# HDMI.net
KiCad netlist of a schematic drawn in Altium Designer
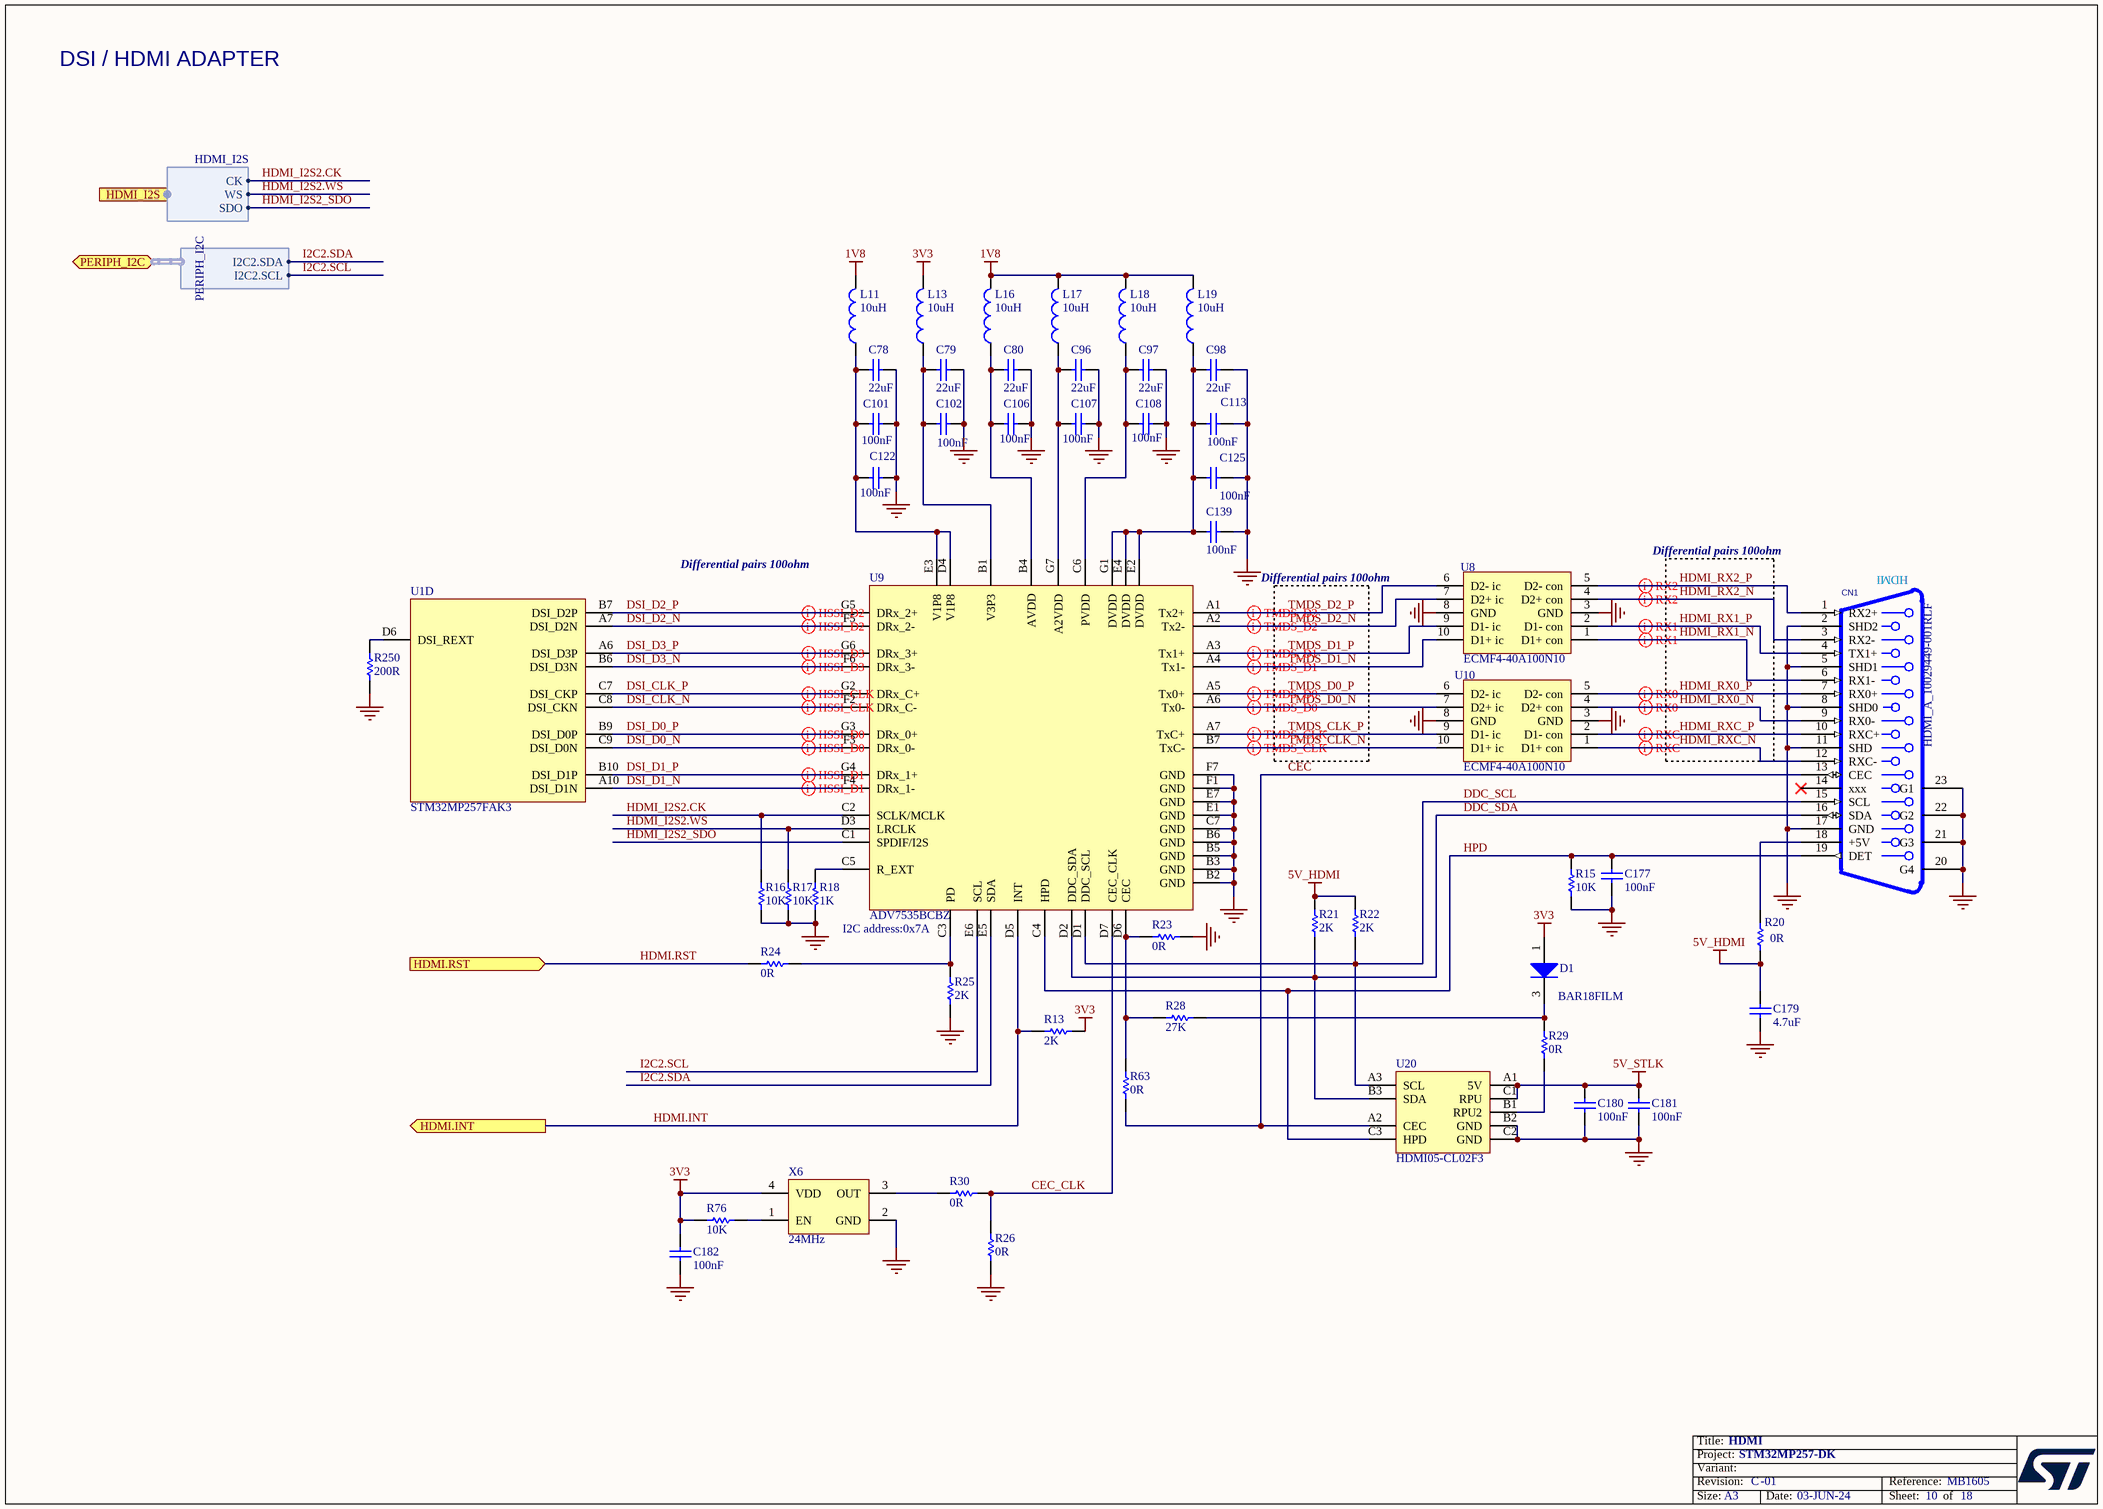
[diagram p0: HDMI.SchDoc]

(export (version "E")
  (design (tool "Eeschema 10.0.6"))
  (components
    (comp (ref "C78")
      (value "22uF")
      (footprint "C0603")
      (description "Capacitor, MLCC, 22uF, 6V3, X5R, +/-20%, 0603, T=0.8mm")
      (fields (field (name "INTERNAL_PART_NUMBER") "MCD-00100") (field (name "MANUFACTURER") "MURATA"))
      (libsource (lib "MCD_PARTS_database") (part "Capacitor"))
    )
    (comp (ref "C79")
      (value "22uF")
      (footprint "C0603")
      (description "Capacitor, MLCC, 22uF, 6V3, X5R, +/-20%, 0603, T=0.8mm")
      (fields (field (name "INTERNAL_PART_NUMBER") "MCD-00100") (field (name "MANUFACTURER") "MURATA"))
      (libsource (lib "MCD_PARTS_database") (part "Capacitor"))
    )
    (comp (ref "C80")
      (value "22uF")
      (footprint "C0603")
      (description "Capacitor, MLCC, 22uF, 6V3, X5R, +/-20%, 0603, T=0.8mm")
      (fields (field (name "INTERNAL_PART_NUMBER") "MCD-00100") (field (name "MANUFACTURER") "MURATA"))
      (libsource (lib "MCD_PARTS_database") (part "Capacitor"))
    )
    (comp (ref "C96")
      (value "22uF")
      (footprint "C0603")
      (description "Capacitor, MLCC, 22uF, 6V3, X5R, +/-20%, 0603, T=0.8mm")
      (fields (field (name "INTERNAL_PART_NUMBER") "MCD-00100") (field (name "MANUFACTURER") "MURATA"))
      (libsource (lib "MCD_PARTS_database") (part "Capacitor"))
    )
    (comp (ref "C97")
      (value "22uF")
      (footprint "C0603")
      (description "Capacitor, MLCC, 22uF, 6V3, X5R, +/-20%, 0603, T=0.8mm")
      (fields (field (name "INTERNAL_PART_NUMBER") "MCD-00100") (field (name "MANUFACTURER") "MURATA"))
      (libsource (lib "MCD_PARTS_database") (part "Capacitor"))
    )
    (comp (ref "C98")
      (value "22uF")
      (footprint "C0603")
      (description "Capacitor, MLCC, 22uF, 6V3, X5R, +/-20%, 0603, T=0.8mm")
      (fields (field (name "INTERNAL_PART_NUMBER") "MCD-00100") (field (name "MANUFACTURER") "MURATA"))
      (libsource (lib "MCD_PARTS_database") (part "Capacitor"))
    )
    (comp (ref "C101")
      (value "100nF")
      (footprint "C0402")
      (description "Capacitor, MLCC, 100nF, 16V, X7R, +/-10%, 0402, T=0.5mm")
      (fields (field (name "INTERNAL_PART_NUMBER") "MCD-00006") (field (name "MANUFACTURER") "YAGEO"))
      (libsource (lib "MCD_PARTS_database") (part "Capacitor"))
    )
    (comp (ref "C102")
      (value "100nF")
      (footprint "C0402")
      (description "Capacitor, MLCC, 100nF, 16V, X7R, +/-10%, 0402, T=0.5mm")
      (fields (field (name "INTERNAL_PART_NUMBER") "MCD-00006") (field (name "MANUFACTURER") "YAGEO"))
      (libsource (lib "MCD_PARTS_database") (part "Capacitor"))
    )
    (comp (ref "C106")
      (value "100nF")
      (footprint "C0402")
      (description "Capacitor, MLCC, 100nF, 16V, X7R, +/-10%, 0402, T=0.5mm")
      (fields (field (name "INTERNAL_PART_NUMBER") "MCD-00006") (field (name "MANUFACTURER") "YAGEO"))
      (libsource (lib "MCD_PARTS_database") (part "Capacitor"))
    )
    (comp (ref "C107")
      (value "100nF")
      (footprint "C0402")
      (description "Capacitor, MLCC, 100nF, 16V, X7R, +/-10%, 0402, T=0.5mm")
      (fields (field (name "INTERNAL_PART_NUMBER") "MCD-00006") (field (name "MANUFACTURER") "YAGEO"))
      (libsource (lib "MCD_PARTS_database") (part "Capacitor"))
    )
    (comp (ref "C108")
      (value "100nF")
      (footprint "C0402")
      (description "Capacitor, MLCC, 100nF, 16V, X7R, +/-10%, 0402, T=0.5mm")
      (fields (field (name "INTERNAL_PART_NUMBER") "MCD-00006") (field (name "MANUFACTURER") "YAGEO"))
      (libsource (lib "MCD_PARTS_database") (part "Capacitor"))
    )
    (comp (ref "C113")
      (value "100nF")
      (footprint "C0402")
      (description "Capacitor, MLCC, 100nF, 16V, X7R, +/-10%, 0402, T=0.5mm")
      (fields (field (name "INTERNAL_PART_NUMBER") "MCD-00006") (field (name "MANUFACTURER") "YAGEO"))
      (libsource (lib "MCD_PARTS_database") (part "Capacitor"))
    )
    (comp (ref "C122")
      (value "100nF")
      (footprint "C0402")
      (description "Capacitor, MLCC, 100nF, 16V, X7R, +/-10%, 0402, T=0.5mm")
      (fields (field (name "INTERNAL_PART_NUMBER") "MCD-00006") (field (name "MANUFACTURER") "YAGEO"))
      (libsource (lib "MCD_PARTS_database") (part "Capacitor"))
    )
    (comp (ref "C125")
      (value "100nF")
      (footprint "C0402")
      (description "Capacitor, MLCC, 100nF, 16V, X7R, +/-10%, 0402, T=0.5mm")
      (fields (field (name "INTERNAL_PART_NUMBER") "MCD-00006") (field (name "MANUFACTURER") "YAGEO"))
      (libsource (lib "MCD_PARTS_database") (part "Capacitor"))
    )
    (comp (ref "C139")
      (value "100nF")
      (footprint "C0402")
      (description "Capacitor, MLCC, 100nF, 16V, X7R, +/-10%, 0402, T=0.5mm")
      (fields (field (name "INTERNAL_PART_NUMBER") "MCD-00006") (field (name "MANUFACTURER") "YAGEO"))
      (libsource (lib "MCD_PARTS_database") (part "Capacitor"))
    )
    (comp (ref "C177")
      (value "100nF")
      (footprint "C0402")
      (description "Capacitor, MLCC, 100nF, 16V, X7R, +/-10%, 0402, T=0.5mm")
      (fields (field (name "INTERNAL_PART_NUMBER") "MCD-00006") (field (name "MANUFACTURER") "YAGEO"))
      (libsource (lib "MCD_PARTS_database") (part "Capacitor"))
    )
    (comp (ref "C179")
      (value "4.7uF")
      (footprint "C0402")
      (description "Capacitor, MLCC, 4.7uF, 6V3, X5R, +/-20%, 0402, T=0.5mm")
      (fields (field (name "INTERNAL_PART_NUMBER") "MCD-01356") (field (name "MANUFACTURER") "MURATA"))
      (libsource (lib "MCD_PARTS_database") (part "Capacitor"))
    )
    (comp (ref "C180")
      (value "100nF")
      (footprint "C0402")
      (description "Capacitor, MLCC, 100nF, 16V, X7R, +/-10%, 0402, T=0.5mm")
      (fields (field (name "INTERNAL_PART_NUMBER") "MCD-00006") (field (name "MANUFACTURER") "YAGEO"))
      (libsource (lib "MCD_PARTS_database") (part "Capacitor"))
    )
    (comp (ref "C181")
      (value "100nF")
      (footprint "C0402")
      (description "Capacitor, MLCC, 100nF, 16V, X7R, +/-10%, 0402, T=0.5mm")
      (fields (field (name "INTERNAL_PART_NUMBER") "MCD-00006") (field (name "MANUFACTURER") "YAGEO"))
      (libsource (lib "MCD_PARTS_database") (part "Capacitor"))
    )
    (comp (ref "C182")
      (value "100nF")
      (footprint "C0402")
      (description "Capacitor, MLCC, 100nF, 16V, X7R, +/-10%, 0402, T=0.5mm")
      (fields (field (name "INTERNAL_PART_NUMBER") "MCD-00006") (field (name "MANUFACTURER") "YAGEO"))
      (libsource (lib "MCD_PARTS_database") (part "Capacitor"))
    )
    (comp (ref "CN1")
      (value "HDMI_A_10029449-001RLF")
      (footprint "CON_HDMI_FCI-AMPHENOL_10029449-001RLF")
      (description "HDMI_Type A, Receptacle, 19x1, 0.5mm, VR, SMD, T= 6.1mm")
      (fields (field (name "INTERNAL_PART_NUMBER") "MCD-00307") (field (name "MANUFACTURER") "AMPHENOL ICC"))
      (libsource (lib "MCD_PARTS_database") (part "HDMI_TypeA_DB19_7"))
    )
    (comp (ref "D1")
      (value "BAR18FILM")
      (footprint "DIO_SOT23_SC59_1A_2NC_3K_H1P4")
      (description "Diode, Ultrafast and RF switching diode, VF=0.41V@IF=1mA, VBR=70V")
      (fields
        (field (name "INTERNAL_PART_NUMBER") "MCD-02333")
        (field (name "MANUFACTURER") "STMICROELECTRONICS")
      )
      (libsource (lib "MCD_PARTS_database") (part "DIODE_SOT23"))
    )
    (comp (ref "L11")
      (value "10uH")
      (footprint "IND_0805_MURATA_LQM21")
      (description "Inductor, 10uH, +/-20%, Isat 100mA, DCR 0.5Ohm,")
      (fields (field (name "INTERNAL_PART_NUMBER") "MCD-02317") (field (name "MANUFACTURER") "MURATA"))
      (libsource (lib "MCD_PARTS_database") (part "Inductor"))
    )
    (comp (ref "L13")
      (value "10uH")
      (footprint "IND_0805_MURATA_LQM21")
      (description "Inductor, 10uH, +/-20%, Isat 100mA, DCR 0.5Ohm,")
      (fields (field (name "INTERNAL_PART_NUMBER") "MCD-02317") (field (name "MANUFACTURER") "MURATA"))
      (libsource (lib "MCD_PARTS_database") (part "Inductor"))
    )
    (comp (ref "L16")
      (value "10uH")
      (footprint "IND_0805_MURATA_LQM21")
      (description "Inductor, 10uH, +/-20%, Isat 100mA, DCR 0.5Ohm,")
      (fields (field (name "INTERNAL_PART_NUMBER") "MCD-02317") (field (name "MANUFACTURER") "MURATA"))
      (libsource (lib "MCD_PARTS_database") (part "Inductor"))
    )
    (comp (ref "L17")
      (value "10uH")
      (footprint "IND_0805_MURATA_LQM21")
      (description "Inductor, 10uH, +/-20%, Isat 100mA, DCR 0.5Ohm,")
      (fields (field (name "INTERNAL_PART_NUMBER") "MCD-02317") (field (name "MANUFACTURER") "MURATA"))
      (libsource (lib "MCD_PARTS_database") (part "Inductor"))
    )
    (comp (ref "L18")
      (value "10uH")
      (footprint "IND_0805_MURATA_LQM21")
      (description "Inductor, 10uH, +/-20%, Isat 100mA, DCR 0.5Ohm,")
      (fields (field (name "INTERNAL_PART_NUMBER") "MCD-02317") (field (name "MANUFACTURER") "MURATA"))
      (libsource (lib "MCD_PARTS_database") (part "Inductor"))
    )
    (comp (ref "L19")
      (value "10uH")
      (footprint "IND_0805_MURATA_LQM21")
      (description "Inductor, 10uH, +/-20%, Isat 100mA, DCR 0.5Ohm,")
      (fields (field (name "INTERNAL_PART_NUMBER") "MCD-02317") (field (name "MANUFACTURER") "MURATA"))
      (libsource (lib "MCD_PARTS_database") (part "Inductor"))
    )
    (comp (ref "R13")
      (value "2K")
      (footprint "R0402")
      (description "Resistor, 2K, 0402, +/-1%, 1/16W")
      (fields (field (name "INTERNAL_PART_NUMBER") "MCD-00419") (field (name "MANUFACTURER") "YAGEO"))
      (libsource (lib "MCD_PARTS_database") (part "Resistor"))
    )
    (comp (ref "R15")
      (value "10K")
      (footprint "R0402")
      (description "Resistor, 10K, 0402, +/-1%, 1/16W")
      (fields (field (name "INTERNAL_PART_NUMBER") "MCD-00053") (field (name "MANUFACTURER") "YAGEO"))
      (libsource (lib "MCD_PARTS_database") (part "Resistor"))
    )
    (comp (ref "R16")
      (value "10K")
      (footprint "R0402")
      (description "Resistor, 10K, 0402, +/-1%, 1/16W")
      (fields (field (name "INTERNAL_PART_NUMBER") "MCD-00053") (field (name "MANUFACTURER") "YAGEO"))
      (libsource (lib "MCD_PARTS_database") (part "Resistor"))
    )
    (comp (ref "R17")
      (value "10K")
      (footprint "R0402")
      (description "Resistor, 10K, 0402, +/-1%, 1/16W")
      (fields (field (name "INTERNAL_PART_NUMBER") "MCD-00053") (field (name "MANUFACTURER") "YAGEO"))
      (libsource (lib "MCD_PARTS_database") (part "Resistor"))
    )
    (comp (ref "R18")
      (value "1K")
      (footprint "R0402")
      (description "Resistor, 1K, 0402, +/-1%,1/16W")
      (fields (field (name "INTERNAL_PART_NUMBER") "MCD-00061") (field (name "MANUFACTURER") "YAGEO"))
      (libsource (lib "MCD_PARTS_database") (part "Resistor"))
    )
    (comp (ref "R20")
      (value "0R")
      (footprint "R0402")
      (description "Resistor, 0R, 0402, +/-5%, 1/16W")
      (fields (field (name "INTERNAL_PART_NUMBER") "MCD-00052") (field (name "MANUFACTURER") "YAGEO"))
      (libsource (lib "MCD_PARTS_database") (part "Resistor"))
    )
    (comp (ref "R21")
      (value "2K")
      (footprint "R0402")
      (description "Resistor, 2K, 0402, +/-1%, 1/16W")
      (fields (field (name "INTERNAL_PART_NUMBER") "MCD-00419") (field (name "MANUFACTURER") "YAGEO"))
      (libsource (lib "MCD_PARTS_database") (part "Resistor"))
    )
    (comp (ref "R22")
      (value "2K")
      (footprint "R0402")
      (description "Resistor, 2K, 0402, +/-1%, 1/16W")
      (fields (field (name "INTERNAL_PART_NUMBER") "MCD-00419") (field (name "MANUFACTURER") "YAGEO"))
      (libsource (lib "MCD_PARTS_database") (part "Resistor"))
    )
    (comp (ref "R23")
      (value "0R")
      (footprint "R0402")
      (description "Resistor, 0R, 0402, +/-5%, 1/16W")
      (fields (field (name "INTERNAL_PART_NUMBER") "MCD-00052") (field (name "MANUFACTURER") "YAGEO"))
      (libsource (lib "MCD_PARTS_database") (part "Resistor"))
    )
    (comp (ref "R24")
      (value "0R")
      (footprint "R0402")
      (description "Resistor, 0R, 0402, +/-5%, 1/16W")
      (fields (field (name "INTERNAL_PART_NUMBER") "MCD-00052") (field (name "MANUFACTURER") "YAGEO"))
      (libsource (lib "MCD_PARTS_database") (part "Resistor"))
    )
    (comp (ref "R25")
      (value "2K")
      (footprint "R0402")
      (description "Resistor, 2K, 0402, +/-1%, 1/16W")
      (fields (field (name "INTERNAL_PART_NUMBER") "MCD-00419") (field (name "MANUFACTURER") "YAGEO"))
      (libsource (lib "MCD_PARTS_database") (part "Resistor"))
    )
    (comp (ref "R26")
      (value "0R")
      (footprint "R0402")
      (description "Resistor, 0R, 0402, +/-5%, 1/16W")
      (fields (field (name "INTERNAL_PART_NUMBER") "MCD-00052") (field (name "MANUFACTURER") "YAGEO"))
      (libsource (lib "MCD_PARTS_database") (part "Resistor"))
    )
    (comp (ref "R28")
      (value "27K")
      (footprint "R0603")
      (description "Resistor, 27K, 0603, +/-1%, 1/10W")
      (fields (field (name "INTERNAL_PART_NUMBER") "MCD-00444") (field (name "MANUFACTURER") "YAGEO"))
      (libsource (lib "MCD_PARTS_database") (part "Resistor"))
    )
    (comp (ref "R29")
      (value "0R")
      (footprint "R0402")
      (description "Resistor, 0R, 0402, +/-5%, 1/16W")
      (fields (field (name "INTERNAL_PART_NUMBER") "MCD-00052") (field (name "MANUFACTURER") "YAGEO"))
      (libsource (lib "MCD_PARTS_database") (part "Resistor"))
    )
    (comp (ref "R30")
      (value "0R")
      (footprint "R0402")
      (description "Resistor, 0R, 0402, +/-5%, 1/16W")
      (fields (field (name "INTERNAL_PART_NUMBER") "MCD-00052") (field (name "MANUFACTURER") "YAGEO"))
      (libsource (lib "MCD_PARTS_database") (part "Resistor"))
    )
    (comp (ref "R63")
      (value "0R")
      (footprint "R0402")
      (description "Resistor, 0R, 0402, +/-5%, 1/16W")
      (fields (field (name "INTERNAL_PART_NUMBER") "MCD-00052") (field (name "MANUFACTURER") "YAGEO"))
      (libsource (lib "MCD_PARTS_database") (part "Resistor"))
    )
    (comp (ref "R76")
      (value "10K")
      (footprint "R0402")
      (description "Resistor, 10K, 0402, +/-1%, 1/16W")
      (fields (field (name "INTERNAL_PART_NUMBER") "MCD-00053") (field (name "MANUFACTURER") "YAGEO"))
      (libsource (lib "MCD_PARTS_database") (part "Resistor"))
    )
    (comp (ref "R250")
      (value "200R")
      (footprint "R0402")
      (description "Resistor, 200R, 0402, +/-1%, 1/16W")
      (fields
        (field (name "INTERNAL_PART_NUMBER") "MCD-00417")
        (field (name "MANUFACTURER_PART_NUMBER") "RC0402FR-07200RL")
      )
      (libsource (lib "MCD_PARTS_database") (part "Resistor"))
    )
    (comp (ref "U1")
      (value "STM32MP257FAK3")
      (footprint "ICC_TFBGA424_14X14_P050_H1P20_CODE-B0A2")
      (description "MPU , 2xCortex-A35@1.5GHz, Cortex-M33@400MHz, TFBGA 14x14, pitch 0.5, 648KB SRAM, With Crypto")
      (fields
        (field (name "INTERNAL_PART_NUMBER") "MCD-03375")
        (field (name "MANUFACTURER") "STMICROELECTRONICS")
      )
      (libsource (lib "MCD_PARTS_database") (part "STM32MP257FAK3"))
    )
    (comp (ref "U8")
      (value "ECMF4-40A100N10")
      (footprint "ESD_UQFN-10L_2P25X1P4_P040")
      (description "ESD protection & Common Filter High Speed serial Interfaces , 0.4 pitch")
      (fields
        (field (name "INTERNAL_PART_NUMBER") "MCD-03059")
        (field (name "MANUFACTURER") "STMICROELECTRONICS")
      )
      (libsource (lib "MCD_PARTS_database") (part "ECMF4-40A100N10"))
    )
    (comp (ref "U9")
      (value "ADV7535BCBZ")
      (footprint "ICC_WLCSP49_3P46X3P46_P050")
      (description "MIPI/DSI Receiver with HDMI Transmitter")
      (fields
        (field (name "INTERNAL_PART_NUMBER") "MCD-02315")
        (field (name "MANUFACTURER") "ANALOG DEVICES")
      )
      (libsource (lib "MCD_PARTS_database") (part "ADV7535BCBZ"))
    )
    (comp (ref "U10")
      (value "ECMF4-40A100N10")
      (footprint "ESD_UQFN-10L_2P25X1P4_P040")
      (description "ESD protection & Common Filter High Speed serial Interfaces , 0.4 pitch")
      (fields
        (field (name "INTERNAL_PART_NUMBER") "MCD-03059")
        (field (name "MANUFACTURER") "STMICROELECTRONICS")
      )
      (libsource (lib "MCD_PARTS_database") (part "ECMF4-40A100N10"))
    )
    (comp (ref "U20")
      (value "HDMI05-CL02F3")
      (footprint "ESD_FLIP-CHIP_BGA9_1P14X1P14_P040")
      (description "5-line HDMI control line ESD protection")
      (fields
        (field (name "INTERNAL_PART_NUMBER") "MCD-02316")
        (field (name "MANUFACTURER") "STMICROELECTRONICS")
      )
      (libsource (lib "MCD_PARTS_database") (part "HDMI05-CL02F3"))
    )
    (comp (ref "X6")
      (value "24MHz")
      (footprint "CRY_NZ2016SH_4P")
      (description "Oscillator, SPXO, 24MHz, +/-50ppm, square wave, 3V3, 2x1.6mm")
      (fields (field (name "INTERNAL_PART_NUMBER") "MCD-01627") (field (name "BMS_PART_NUMBER") "9157051"))
      (libsource (lib "MCD_PARTS_database") (part "OSCILLATOR_4_PINS"))
    )
  )
  (nets
    (net (code "3") (name "/CEC") (class "Default")
      (node (ref "CN1") (pin "13") (pinfunction "CEC_13") (pintype "bidirectional"))
      (node (ref "R63") (pin "1") (pinfunction "1_1") (pintype "passive"))
      (node (ref "U20") (pin "A2") (pinfunction "CEC_A2") (pintype "passive"))
    )
    (net (code "4") (name "/CEC_CLK") (class "Default")
      (node (ref "R26") (pin "2") (pinfunction "2_2") (pintype "passive"))
      (node (ref "R30") (pin "1") (pinfunction "1_1") (pintype "passive"))
      (node (ref "U9") (pin "D7") (pinfunction "CEC_CLK_D7") (pintype "passive"))
    )
    (net (code "5") (name "/DDC_SCL") (class "Default")
      (node (ref "CN1") (pin "15") (pinfunction "SCL_15") (pintype "input"))
      (node (ref "R22") (pin "1") (pinfunction "1_1") (pintype "passive"))
      (node (ref "U20") (pin "A3") (pinfunction "SCL_A3") (pintype "passive"))
      (node (ref "U9") (pin "D1") (pinfunction "DDC_SCL_D1") (pintype "passive"))
    )
    (net (code "6") (name "/DDC_SDA") (class "Default")
      (node (ref "CN1") (pin "16") (pinfunction "SDA_16") (pintype "bidirectional"))
      (node (ref "R21") (pin "1") (pinfunction "1_1") (pintype "passive"))
      (node (ref "U20") (pin "B3") (pinfunction "SDA_B3") (pintype "passive"))
      (node (ref "U9") (pin "D2") (pinfunction "DDC_SDA_D2") (pintype "passive"))
    )
    (net (code "7") (name "/DSI_CLK_N") (class "Default")
      (node (ref "U1") (pin "C8") (pinfunction "DSI_CKN_C8") (pintype "passive"))
      (node (ref "U9") (pin "F2") (pinfunction "DRx_C-_F2") (pintype "passive"))
    )
    (net (code "8") (name "/DSI_CLK_P") (class "Default")
      (node (ref "U1") (pin "C7") (pinfunction "DSI_CKP_C7") (pintype "passive"))
      (node (ref "U9") (pin "G2") (pinfunction "DRx_C+_G2") (pintype "passive"))
    )
    (net (code "9") (name "/DSI_D0_N") (class "Default")
      (node (ref "U1") (pin "C9") (pinfunction "DSI_D0N_C9") (pintype "passive"))
      (node (ref "U9") (pin "F3") (pinfunction "DRx_0-_F3") (pintype "passive"))
    )
    (net (code "10") (name "/DSI_D0_P") (class "Default")
      (node (ref "U1") (pin "B9") (pinfunction "DSI_D0P_B9") (pintype "passive"))
      (node (ref "U9") (pin "G3") (pinfunction "DRx_0+_G3") (pintype "passive"))
    )
    (net (code "11") (name "/DSI_D1_N") (class "Default")
      (node (ref "U1") (pin "A10") (pinfunction "DSI_D1N_A10") (pintype "passive"))
      (node (ref "U9") (pin "F4") (pinfunction "DRx_1-_F4") (pintype "passive"))
    )
    (net (code "12") (name "/DSI_D1_P") (class "Default")
      (node (ref "U1") (pin "B10") (pinfunction "DSI_D1P_B10") (pintype "passive"))
      (node (ref "U9") (pin "G4") (pinfunction "DRx_1+_G4") (pintype "passive"))
    )
    (net (code "13") (name "/DSI_D2_N") (class "Default")
      (node (ref "U1") (pin "A7") (pinfunction "DSI_D2N_A7") (pintype "passive"))
      (node (ref "U9") (pin "F5") (pinfunction "DRx_2-_F5") (pintype "passive"))
    )
    (net (code "14") (name "/DSI_D2_P") (class "Default")
      (node (ref "U1") (pin "B7") (pinfunction "DSI_D2P_B7") (pintype "passive"))
      (node (ref "U9") (pin "G5") (pinfunction "DRx_2+_G5") (pintype "passive"))
    )
    (net (code "15") (name "/DSI_D3_N") (class "Default")
      (node (ref "U1") (pin "B6") (pinfunction "DSI_D3N_B6") (pintype "passive"))
      (node (ref "U9") (pin "F6") (pinfunction "DRx_3-_F6") (pintype "passive"))
    )
    (net (code "16") (name "/DSI_D3_P") (class "Default")
      (node (ref "U1") (pin "A6") (pinfunction "DSI_D3P_A6") (pintype "passive"))
      (node (ref "U9") (pin "G6") (pinfunction "DRx_3+_G6") (pintype "passive"))
    )
    (net (code "17") (name "/HDMI.INT") (class "Default")
      (node (ref "R13") (pin "2") (pinfunction "2_2") (pintype "passive"))
      (node (ref "U9") (pin "D5") (pinfunction "INT_D5") (pintype "passive"))
    )
    (net (code "18") (name "/HDMI.RST") (class "Default")
      (node (ref "R24") (pin "1") (pinfunction "1_1") (pintype "passive"))
    )
    (net (code "19") (name "/HDMI_I2S2.CK") (class "Default")
      (node (ref "R16") (pin "2") (pinfunction "2_2") (pintype "passive"))
      (node (ref "U9") (pin "C2") (pinfunction "SCLK/MCLK_C2") (pintype "passive"))
    )
    (net (code "20") (name "/HDMI_I2S2.WS") (class "Default")
      (node (ref "R17") (pin "2") (pinfunction "2_2") (pintype "passive"))
      (node (ref "U9") (pin "D3") (pinfunction "LRCLK_D3") (pintype "passive"))
    )
    (net (code "21") (name "/HDMI_I2S2_SDO") (class "Default")
      (node (ref "U9") (pin "C1") (pinfunction "SPDIF/I2S_C1") (pintype "passive"))
    )
    (net (code "22") (name "/HDMI_RX0_N") (class "Default")
      (node (ref "CN1") (pin "9") (pinfunction "RX0-_9") (pintype "input"))
      (node (ref "U10") (pin "4") (pinfunction "D2+_con_4") (pintype "passive"))
    )
    (net (code "23") (name "/HDMI_RX0_P") (class "Default")
      (node (ref "CN1") (pin "7") (pinfunction "RX0+_7") (pintype "input"))
      (node (ref "U10") (pin "5") (pinfunction "D2-_con_5") (pintype "passive"))
    )
    (net (code "24") (name "/HDMI_RX1_N") (class "Default")
      (node (ref "CN1") (pin "6") (pinfunction "RX1-_6") (pintype "input"))
      (node (ref "U8") (pin "1") (pinfunction "D1+_con_1") (pintype "passive"))
    )
    (net (code "25") (name "/HDMI_RX1_P") (class "Default")
      (node (ref "CN1") (pin "4") (pinfunction "TX1+_4") (pintype "input"))
      (node (ref "U8") (pin "2") (pinfunction "D1-_con_2") (pintype "passive"))
    )
    (net (code "26") (name "/HDMI_RX2_N") (class "Default")
      (node (ref "CN1") (pin "3") (pinfunction "RX2-_3") (pintype "input"))
      (node (ref "U8") (pin "4") (pinfunction "D2+_con_4") (pintype "passive"))
    )
    (net (code "27") (name "/HDMI_RX2_P") (class "Default")
      (node (ref "CN1") (pin "1") (pinfunction "RX2+_1") (pintype "input"))
      (node (ref "U8") (pin "5") (pinfunction "D2-_con_5") (pintype "passive"))
    )
    (net (code "28") (name "/HDMI_RXC_N") (class "Default")
      (node (ref "CN1") (pin "12") (pinfunction "RXC-_12") (pintype "input"))
      (node (ref "U10") (pin "1") (pinfunction "D1+_con_1") (pintype "passive"))
    )
    (net (code "29") (name "/HDMI_RXC_P") (class "Default")
      (node (ref "CN1") (pin "10") (pinfunction "RXC+_10") (pintype "input"))
      (node (ref "U10") (pin "2") (pinfunction "D1-_con_2") (pintype "passive"))
    )
    (net (code "30") (name "/HPD") (class "Default")
      (node (ref "C177") (pin "2") (pinfunction "2_2") (pintype "passive"))
      (node (ref "CN1") (pin "19") (pinfunction "DET_19") (pintype "output"))
      (node (ref "R15") (pin "1") (pinfunction "1_1") (pintype "passive"))
      (node (ref "U20") (pin "C3") (pinfunction "HPD_C3") (pintype "passive"))
      (node (ref "U9") (pin "C4") (pinfunction "HPD_C4") (pintype "passive"))
    )
    (net (code "31") (name "/I2C2.SCL") (class "Default")
      (node (ref "U9") (pin "E6") (pinfunction "SCL_E6") (pintype "passive"))
    )
    (net (code "32") (name "/I2C2.SDA") (class "Default")
      (node (ref "U9") (pin "E5") (pinfunction "SDA_E5") (pintype "passive"))
    )
    (net (code "33") (name "/TMDS_CLK_N") (class "Default")
      (node (ref "U10") (pin "10") (pinfunction "D1+_ic_10") (pintype "passive"))
      (node (ref "U9") (pin "B7") (pinfunction "TxC-_B7") (pintype "passive"))
    )
    (net (code "34") (name "/TMDS_CLK_P") (class "Default")
      (node (ref "U10") (pin "9") (pinfunction "D1-_ic_9") (pintype "passive"))
      (node (ref "U9") (pin "A7") (pinfunction "TxC+_A7") (pintype "passive"))
    )
    (net (code "35") (name "/TMDS_D0_N") (class "Default")
      (node (ref "U10") (pin "7") (pinfunction "D2+_ic_7") (pintype "passive"))
      (node (ref "U9") (pin "A6") (pinfunction "Tx0-_A6") (pintype "passive"))
    )
    (net (code "36") (name "/TMDS_D0_P") (class "Default")
      (node (ref "U10") (pin "6") (pinfunction "D2-_ic_6") (pintype "passive"))
      (node (ref "U9") (pin "A5") (pinfunction "Tx0+_A5") (pintype "passive"))
    )
    (net (code "37") (name "/TMDS_D1_N") (class "Default")
      (node (ref "U8") (pin "10") (pinfunction "D1+_ic_10") (pintype "passive"))
      (node (ref "U9") (pin "A4") (pinfunction "Tx1-_A4") (pintype "passive"))
    )
    (net (code "38") (name "/TMDS_D1_P") (class "Default")
      (node (ref "U8") (pin "9") (pinfunction "D1-_ic_9") (pintype "passive"))
      (node (ref "U9") (pin "A3") (pinfunction "Tx1+_A3") (pintype "passive"))
    )
    (net (code "39") (name "/TMDS_D2_N") (class "Default")
      (node (ref "U8") (pin "7") (pinfunction "D2+_ic_7") (pintype "passive"))
      (node (ref "U9") (pin "A2") (pinfunction "Tx2-_A2") (pintype "passive"))
    )
    (net (code "40") (name "/TMDS_D2_P") (class "Default")
      (node (ref "U8") (pin "6") (pinfunction "D2-_ic_6") (pintype "passive"))
      (node (ref "U9") (pin "A1") (pinfunction "Tx2+_A1") (pintype "passive"))
    )
    (net (code "43") (name "1V8") (class "Default")
      (node (ref "L11") (pin "2") (pinfunction "2_2") (pintype "passive"))
      (node (ref "L16") (pin "2") (pinfunction "2_2") (pintype "passive"))
      (node (ref "L17") (pin "2") (pinfunction "2_2") (pintype "passive"))
      (node (ref "L18") (pin "2") (pinfunction "2_2") (pintype "passive"))
      (node (ref "L19") (pin "2") (pinfunction "2_2") (pintype "passive"))
    )
    (net (code "44") (name "3V3") (class "Default")
      (node (ref "C182") (pin "2") (pinfunction "2_2") (pintype "passive"))
      (node (ref "D1") (pin "1") (pinfunction "A_1") (pintype "passive"))
      (node (ref "L13") (pin "2") (pinfunction "2_2") (pintype "passive"))
      (node (ref "R13") (pin "1") (pinfunction "1_1") (pintype "passive"))
      (node (ref "R76") (pin "1") (pinfunction "1_1") (pintype "passive"))
      (node (ref "X6") (pin "4") (pinfunction "VDD_4") (pintype "passive"))
    )
    (net (code "45") (name "5V_HDMI") (class "Default")
      (node (ref "C179") (pin "2") (pinfunction "2_2") (pintype "passive"))
      (node (ref "R20") (pin "1") (pinfunction "1_1") (pintype "passive"))
      (node (ref "R21") (pin "2") (pinfunction "2_2") (pintype "passive"))
      (node (ref "R22") (pin "2") (pinfunction "2_2") (pintype "passive"))
    )
    (net (code "46") (name "5V_STLK") (class "Default")
      (node (ref "C180") (pin "2") (pinfunction "2_2") (pintype "passive"))
      (node (ref "C181") (pin "2") (pinfunction "2_2") (pintype "passive"))
      (node (ref "U20") (pin "A1") (pinfunction "5V_A1") (pintype "passive"))
      (node (ref "U20") (pin "C1") (pinfunction "RPU_C1") (pintype "passive"))
    )
    (net (code "47") (name "GND") (class "Default")
      (node (ref "C101") (pin "1") (pinfunction "1_1") (pintype "passive"))
      (node (ref "C102") (pin "2") (pinfunction "2_2") (pintype "passive"))
      (node (ref "C106") (pin "2") (pinfunction "2_2") (pintype "passive"))
      (node (ref "C107") (pin "2") (pinfunction "2_2") (pintype "passive"))
      (node (ref "C108") (pin "1") (pinfunction "1_1") (pintype "passive"))
      (node (ref "C113") (pin "1") (pinfunction "1_1") (pintype "passive"))
      (node (ref "C122") (pin "1") (pinfunction "1_1") (pintype "passive"))
      (node (ref "C125") (pin "1") (pinfunction "1_1") (pintype "passive"))
      (node (ref "C139") (pin "1") (pinfunction "1_1") (pintype "passive"))
      (node (ref "C177") (pin "1") (pinfunction "1_1") (pintype "passive"))
      (node (ref "C179") (pin "1") (pinfunction "1_1") (pintype "passive"))
      (node (ref "C180") (pin "1") (pinfunction "1_1") (pintype "passive"))
      (node (ref "C181") (pin "1") (pinfunction "1_1") (pintype "passive"))
      (node (ref "C182") (pin "1") (pinfunction "1_1") (pintype "passive"))
      (node (ref "C78") (pin "2") (pinfunction "2_2") (pintype "passive"))
      (node (ref "C79") (pin "2") (pinfunction "2_2") (pintype "passive"))
      (node (ref "C80") (pin "2") (pinfunction "2_2") (pintype "passive"))
      (node (ref "C96") (pin "2") (pinfunction "2_2") (pintype "passive"))
      (node (ref "C97") (pin "2") (pinfunction "2_2") (pintype "passive"))
      (node (ref "C98") (pin "2") (pinfunction "2_2") (pintype "passive"))
      (node (ref "CN1") (pin "11") (pinfunction "SHD_11") (pintype "passive"))
      (node (ref "CN1") (pin "17") (pinfunction "GND_17") (pintype "passive"))
      (node (ref "CN1") (pin "2") (pinfunction "SHD2_2") (pintype "passive"))
      (node (ref "CN1") (pin "20") (pinfunction "G4_20") (pintype "passive"))
      (node (ref "CN1") (pin "21") (pinfunction "G3_21") (pintype "passive"))
      (node (ref "CN1") (pin "22") (pinfunction "G2_22") (pintype "passive"))
      (node (ref "CN1") (pin "23") (pinfunction "G1_23") (pintype "passive"))
      (node (ref "CN1") (pin "5") (pinfunction "SHD1_5") (pintype "passive"))
      (node (ref "CN1") (pin "8") (pinfunction "SHD0_8") (pintype "passive"))
      (node (ref "R15") (pin "2") (pinfunction "2_2") (pintype "passive"))
      (node (ref "R16") (pin "1") (pinfunction "1_1") (pintype "passive"))
      (node (ref "R17") (pin "1") (pinfunction "1_1") (pintype "passive"))
      (node (ref "R18") (pin "1") (pinfunction "1_1") (pintype "passive"))
      (node (ref "R23") (pin "2") (pinfunction "2_2") (pintype "passive"))
      (node (ref "R25") (pin "2") (pinfunction "2_2") (pintype "passive"))
      (node (ref "R250") (pin "2") (pinfunction "2_2") (pintype "passive"))
      (node (ref "R26") (pin "1") (pinfunction "1_1") (pintype "passive"))
      (node (ref "U10") (pin "3") (pinfunction "GND_3") (pintype "passive"))
      (node (ref "U10") (pin "8") (pinfunction "GND_8") (pintype "passive"))
      (node (ref "U20") (pin "B2") (pinfunction "GND_B2") (pintype "passive"))
      (node (ref "U20") (pin "C2") (pinfunction "GND_C2") (pintype "passive"))
      (node (ref "U8") (pin "3") (pinfunction "GND_3") (pintype "passive"))
      (node (ref "U8") (pin "8") (pinfunction "GND_8") (pintype "passive"))
      (node (ref "U9") (pin "B2") (pinfunction "GND_B2") (pintype "passive"))
      (node (ref "U9") (pin "B3") (pinfunction "GND_B3") (pintype "passive"))
      (node (ref "U9") (pin "B5") (pinfunction "GND_B5") (pintype "passive"))
      (node (ref "U9") (pin "B6") (pinfunction "GND_B6") (pintype "passive"))
      (node (ref "U9") (pin "C7") (pinfunction "GND_C7") (pintype "passive"))
      (node (ref "U9") (pin "E1") (pinfunction "GND_E1") (pintype "passive"))
      (node (ref "U9") (pin "E7") (pinfunction "GND_E7") (pintype "passive"))
      (node (ref "U9") (pin "F1") (pinfunction "GND_F1") (pintype "passive"))
      (node (ref "U9") (pin "F7") (pinfunction "GND_F7") (pintype "passive"))
      (node (ref "X6") (pin "2") (pinfunction "GND_2") (pintype "passive"))
    )
    (net (code "48") (name "Net-(C101-Pad2)") (class "Default")
      (node (ref "C101") (pin "2") (pinfunction "2_2") (pintype "passive"))
      (node (ref "C122") (pin "2") (pinfunction "2_2") (pintype "passive"))
      (node (ref "C78") (pin "1") (pinfunction "1_1") (pintype "passive"))
      (node (ref "L11") (pin "1") (pinfunction "1_1") (pintype "passive"))
      (node (ref "U9") (pin "D4") (pinfunction "V1P8_D4") (pintype "passive"))
      (node (ref "U9") (pin "E3") (pinfunction "V1P8_E3") (pintype "passive"))
    )
    (net (code "49") (name "Net-(C113-Pad2)") (class "Default")
      (node (ref "C113") (pin "2") (pinfunction "2_2") (pintype "passive"))
      (node (ref "C125") (pin "2") (pinfunction "2_2") (pintype "passive"))
      (node (ref "C139") (pin "2") (pinfunction "2_2") (pintype "passive"))
      (node (ref "C98") (pin "1") (pinfunction "1_1") (pintype "passive"))
      (node (ref "L19") (pin "1") (pinfunction "1_1") (pintype "passive"))
      (node (ref "U9") (pin "E2") (pinfunction "DVDD_E2") (pintype "passive"))
      (node (ref "U9") (pin "E4") (pinfunction "DVDD_E4") (pintype "passive"))
      (node (ref "U9") (pin "G1") (pinfunction "DVDD_G1") (pintype "passive"))
    )
    (net (code "50") (name "Net-(CN1-+5V)") (class "Default")
      (node (ref "CN1") (pin "18") (pinfunction "+5V_18") (pintype "power_in"))
      (node (ref "R20") (pin "2") (pinfunction "2_2") (pintype "passive"))
    )
    (net (code "51") (name "Net-(D1-K)") (class "Default")
      (node (ref "D1") (pin "3") (pinfunction "K_3") (pintype "passive"))
      (node (ref "R28") (pin "1") (pinfunction "1_1") (pintype "passive"))
      (node (ref "R29") (pin "2") (pinfunction "2_2") (pintype "passive"))
    )
    (net (code "52") (name "Net-(U1D-DSI_REXT)") (class "Default")
      (node (ref "R250") (pin "1") (pinfunction "1_1") (pintype "passive"))
      (node (ref "U1") (pin "D6") (pinfunction "DSI_REXT_D6") (pintype "passive"))
    )
    (net (code "53") (name "Net-(U9-A2VDD)") (class "Default")
      (node (ref "C107") (pin "1") (pinfunction "1_1") (pintype "passive"))
      (node (ref "C96") (pin "1") (pinfunction "1_1") (pintype "passive"))
      (node (ref "L17") (pin "1") (pinfunction "1_1") (pintype "passive"))
      (node (ref "U9") (pin "G7") (pinfunction "A2VDD_G7") (pintype "passive"))
    )
    (net (code "54") (name "Net-(U9-AVDD)") (class "Default")
      (node (ref "C106") (pin "1") (pinfunction "1_1") (pintype "passive"))
      (node (ref "C80") (pin "1") (pinfunction "1_1") (pintype "passive"))
      (node (ref "L16") (pin "1") (pinfunction "1_1") (pintype "passive"))
      (node (ref "U9") (pin "B4") (pinfunction "AVDD_B4") (pintype "passive"))
    )
    (net (code "55") (name "Net-(U9-CEC)") (class "Default")
      (node (ref "R23") (pin "1") (pinfunction "1_1") (pintype "passive"))
      (node (ref "R28") (pin "2") (pinfunction "2_2") (pintype "passive"))
      (node (ref "R63") (pin "2") (pinfunction "2_2") (pintype "passive"))
      (node (ref "U9") (pin "D6") (pinfunction "CEC_D6") (pintype "passive"))
    )
    (net (code "56") (name "Net-(U9-PD)") (class "Default")
      (node (ref "R24") (pin "2") (pinfunction "2_2") (pintype "passive"))
      (node (ref "R25") (pin "1") (pinfunction "1_1") (pintype "passive"))
      (node (ref "U9") (pin "C3") (pinfunction "PD_C3") (pintype "passive"))
    )
    (net (code "57") (name "Net-(U9-PVDD)") (class "Default")
      (node (ref "C108") (pin "2") (pinfunction "2_2") (pintype "passive"))
      (node (ref "C97") (pin "1") (pinfunction "1_1") (pintype "passive"))
      (node (ref "L18") (pin "1") (pinfunction "1_1") (pintype "passive"))
      (node (ref "U9") (pin "C6") (pinfunction "PVDD_C6") (pintype "passive"))
    )
    (net (code "58") (name "Net-(U9-R_EXT)") (class "Default")
      (node (ref "R18") (pin "2") (pinfunction "2_2") (pintype "passive"))
      (node (ref "U9") (pin "C5") (pinfunction "R_EXT_C5") (pintype "passive"))
    )
    (net (code "59") (name "Net-(U9-V3P3)") (class "Default")
      (node (ref "C102") (pin "1") (pinfunction "1_1") (pintype "passive"))
      (node (ref "C79") (pin "1") (pinfunction "1_1") (pintype "passive"))
      (node (ref "L13") (pin "1") (pinfunction "1_1") (pintype "passive"))
      (node (ref "U9") (pin "B1") (pinfunction "V3P3_B1") (pintype "passive"))
    )
    (net (code "60") (name "Net-(U20-RPU2)") (class "Default")
      (node (ref "R29") (pin "1") (pinfunction "1_1") (pintype "passive"))
      (node (ref "U20") (pin "B1") (pinfunction "RPU2_B1") (pintype "passive"))
    )
    (net (code "61") (name "Net-(X6-EN)") (class "Default")
      (node (ref "R76") (pin "2") (pinfunction "2_2") (pintype "passive"))
      (node (ref "X6") (pin "1") (pinfunction "EN_1") (pintype "passive"))
    )
    (net (code "62") (name "Net-(X6-OUT)") (class "Default")
      (node (ref "R30") (pin "2") (pinfunction "2_2") (pintype "passive"))
      (node (ref "X6") (pin "3") (pinfunction "OUT_3") (pintype "passive"))
    )
    (net (code "63") (name "unconnected-(CN1-xxx-Pad14)") (class "Default")
      (node (ref "CN1") (pin "14") (pinfunction "xxx_14") (pintype "passive+no_connect"))
    )
  )
)
